# Motor_Driver_DRV8313.net
KiCad netlist of a schematic drawn in Altium Designer
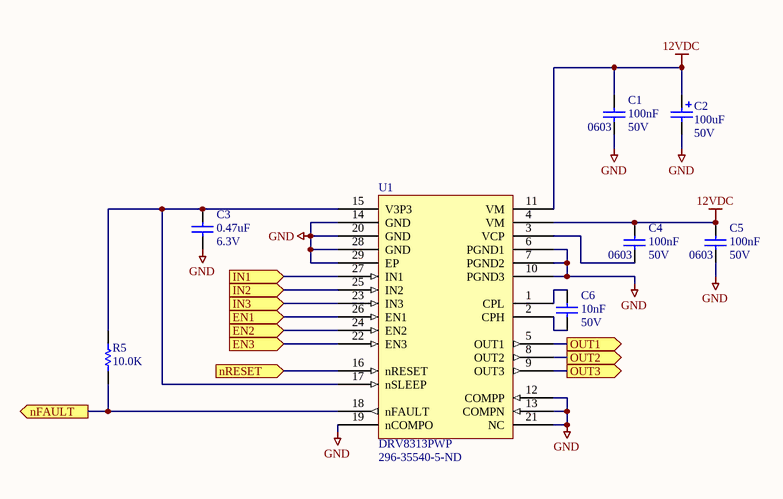
[diagram p0: Motor_Driver_DRV8313.SchDoc]

(export (version "E")
  (design (tool "Eeschema 10.0.6"))
  (components
    (comp (ref "C1")
      (value "100nF")
      (footprint "CAPC1608N(0603\")")
      (description "CAP CER 0.1UF 50V X7R 0603")
      (fields
        (field (name "MANUFACTURER") "Samsung")
        (field (name "MANUFACTURER PART NUMBER") "CL10B104KB8SFNC")
        (field (name "CASE CODE (IMPERIAL)") "0603")
        (field (name "VOLTAGE RATING") "50V")
      )
      (libsource (lib "BLDC_Gimbal_Lib") (part "CL10B104KB8SFNC"))
    )
    (comp (ref "C2")
      (value "100uF")
      (footprint "CAPAE10083X105M")
      (description "Capacitor, Polarized, Aluminum, 50V, +/- 20%, SMD")
      (fields
        (field (name "MFG") "Panasonic")
        (field (name "VOLTAGE") "50V")
        (field (name "PUBLISHER") "UVic AERO, Taylor Long")
      )
      (libsource (lib "AERO Integrated Library - Capacitors") (part "100uF 50V, SMD, Alum, Polarized"))
    )
    (comp (ref "C3")
      (value "0.47uF")
      (footprint "CAPC1608N(0603\")")
      (description "Capacitor, Ceramic, 6.3V, +/- 10%, 0603 SMD, X7R")
      (fields
        (field (name "MFG") "Murata Electronics North America")
        (field (name "VOLTAGE") "6.3V")
        (field (name "PUBLISHER") "UVic AERO, Taylor Long")
      )
      (libsource (lib "AERO Integrated Library - Capacitors") (part "0.47uF 6.3V 0603 SMD, Ceramic"))
    )
    (comp (ref "C4")
      (value "100nF")
      (footprint "CAPC1608N(0603\")")
      (description "CAP CER 0.1UF 50V X7R 0603")
      (fields
        (field (name "MANUFACTURER") "Samsung")
        (field (name "MANUFACTURER PART NUMBER") "CL10B104KB8SFNC")
        (field (name "CASE CODE (IMPERIAL)") "0603")
        (field (name "VOLTAGE RATING") "50V")
      )
      (libsource (lib "BLDC_Gimbal_Lib") (part "CL10B104KB8SFNC"))
    )
    (comp (ref "C5")
      (value "100nF")
      (footprint "CAPC1608N(0603\")")
      (description "CAP CER 0.1UF 50V X7R 0603")
      (fields
        (field (name "MANUFACTURER") "Samsung")
        (field (name "MANUFACTURER PART NUMBER") "CL10B104KB8SFNC")
        (field (name "CASE CODE (IMPERIAL)") "0603")
        (field (name "VOLTAGE RATING") "50V")
      )
      (libsource (lib "BLDC_Gimbal_Lib") (part "CL10B104KB8SFNC"))
    )
    (comp (ref "C6")
      (value "10nF")
      (footprint "CAPC1608N(0603\")")
      (description "Capacitor, Ceramic, 50V, +/- 10%, 0603 SMD, X7R")
      (fields (field (name "VOLTAGE") "50V") (field (name "PUBLISHER") "UVic AERO"))
      (libsource (lib "AERO Schematic Library - Capacitors") (part "10nF 50V 0603 SMD, Ceramic"))
    )
    (comp (ref "R5")
      (value "10.0K")
      (footprint "RESC1608N(0603\")")
      (description "Resistor, 1%, 1/10 W, 0603 SMD, 10.0K, +/-100ppm/C, Thick Film")
      (fields (field (name "POWER") "1/10W") (field (name "PUBLISHER") "TRAXX Automation Ltd."))
      (libsource (lib "AERO Integrated Library - Resistors") (part "10.0K, 1%, 1/10 W, 0603 SMD"))
    )
    (comp (ref "U1")
      (value "DRV8313PWP")
      (footprint "HTSSOP-28")
      (description "DRV8313 2.5-A Triple 1/2-H Bridge Driver")
      (fields
        (field (name "MFG") "Texas Instruments")
        (field (name "SUPPLIER PART NUMBER 1") "296-35540-5-ND")
        (field (name "PUBLISHER") "UVic AERO, Taylor Long")
        (field (name "REVIEWEDBY") "*")
      )
      (libsource (lib "BLDC_Gimbal_Lib") (part "DRV8313PWP"))
    )
  )
  (nets
    (net (code "1") (name "/EN1") (class "Default")
      (node (ref "U1") (pin "26") (pinfunction "EN1_26") (pintype "input"))
    )
    (net (code "2") (name "/EN2") (class "Default")
      (node (ref "U1") (pin "24") (pinfunction "EN2_24") (pintype "input"))
    )
    (net (code "3") (name "/EN3") (class "Default")
      (node (ref "U1") (pin "22") (pinfunction "EN3_22") (pintype "input"))
    )
    (net (code "4") (name "/IN1") (class "Default")
      (node (ref "U1") (pin "27") (pinfunction "IN1_27") (pintype "input"))
    )
    (net (code "5") (name "/IN2") (class "Default")
      (node (ref "U1") (pin "25") (pinfunction "IN2_25") (pintype "input"))
    )
    (net (code "6") (name "/IN3") (class "Default")
      (node (ref "U1") (pin "23") (pinfunction "IN3_23") (pintype "input"))
    )
    (net (code "7") (name "/OUT1") (class "Default")
      (node (ref "U1") (pin "5") (pinfunction "OUT1_5") (pintype "output"))
    )
    (net (code "8") (name "/OUT2") (class "Default")
      (node (ref "U1") (pin "8") (pinfunction "OUT2_8") (pintype "output"))
    )
    (net (code "9") (name "/OUT3") (class "Default")
      (node (ref "U1") (pin "9") (pinfunction "OUT3_9") (pintype "output"))
    )
    (net (code "10") (name "/nFAULT") (class "Default")
      (node (ref "R5") (pin "1") (pinfunction "1_1") (pintype "passive"))
      (node (ref "U1") (pin "18") (pinfunction "nFAULT_18") (pintype "output"))
    )
    (net (code "11") (name "/nRESET") (class "Default")
      (node (ref "U1") (pin "16") (pinfunction "nRESET_16") (pintype "input"))
    )
    (net (code "12") (name "12VDC") (class "Default")
      (node (ref "C1") (pin "2") (pinfunction "2_2") (pintype "passive"))
      (node (ref "C2") (pin "1") (pinfunction "1_1") (pintype "passive"))
      (node (ref "C4") (pin "2") (pinfunction "2_2") (pintype "passive"))
      (node (ref "C5") (pin "2") (pinfunction "2_2") (pintype "passive"))
      (node (ref "U1") (pin "11") (pinfunction "VM_11") (pintype "power_in"))
      (node (ref "U1") (pin "4") (pinfunction "VM_4") (pintype "power_in"))
    )
    (net (code "13") (name "GND") (class "Default")
      (node (ref "C1") (pin "1") (pinfunction "1_1") (pintype "passive"))
      (node (ref "C2") (pin "2") (pinfunction "2_2") (pintype "passive"))
      (node (ref "C3") (pin "2") (pinfunction "2_2") (pintype "passive"))
      (node (ref "C5") (pin "1") (pinfunction "1_1") (pintype "passive"))
      (node (ref "U1") (pin "10") (pinfunction "PGND3_10") (pintype "power_in"))
      (node (ref "U1") (pin "12") (pinfunction "COMPP_12") (pintype "input"))
      (node (ref "U1") (pin "13") (pinfunction "COMPN_13") (pintype "input"))
      (node (ref "U1") (pin "14") (pinfunction "GND_14") (pintype "power_in"))
      (node (ref "U1") (pin "19") (pinfunction "nCOMPO_19") (pintype "passive"))
      (node (ref "U1") (pin "20") (pinfunction "GND_20") (pintype "power_in"))
      (node (ref "U1") (pin "21") (pinfunction "NC_21") (pintype "passive"))
      (node (ref "U1") (pin "28") (pinfunction "GND_28") (pintype "passive"))
      (node (ref "U1") (pin "29") (pinfunction "EP_29") (pintype "passive"))
      (node (ref "U1") (pin "6") (pinfunction "PGND1_6") (pintype "power_in"))
      (node (ref "U1") (pin "7") (pinfunction "PGND2_7") (pintype "power_in"))
    )
    (net (code "14") (name "Net-(U1-CPH)") (class "Default")
      (node (ref "C6") (pin "1") (pinfunction "1_1") (pintype "passive"))
      (node (ref "U1") (pin "2") (pinfunction "CPH_2") (pintype "power_in"))
    )
    (net (code "15") (name "Net-(U1-CPL)") (class "Default")
      (node (ref "C6") (pin "2") (pinfunction "2_2") (pintype "passive"))
      (node (ref "U1") (pin "1") (pinfunction "CPL_1") (pintype "power_in"))
    )
    (net (code "16") (name "Net-(U1-V3P3)") (class "Default")
      (node (ref "C3") (pin "1") (pinfunction "1_1") (pintype "passive"))
      (node (ref "R5") (pin "2") (pinfunction "2_2") (pintype "passive"))
      (node (ref "U1") (pin "15") (pinfunction "V3P3_15") (pintype "power_in"))
      (node (ref "U1") (pin "17") (pinfunction "nSLEEP_17") (pintype "input"))
    )
    (net (code "17") (name "Net-(U1-VCP)") (class "Default")
      (node (ref "C4") (pin "1") (pinfunction "1_1") (pintype "passive"))
      (node (ref "U1") (pin "3") (pinfunction "VCP_3") (pintype "power_in"))
    )
  )
)
